# Sheet_MAGJACK.net
KiCad netlist of a schematic drawn in Altium Designer
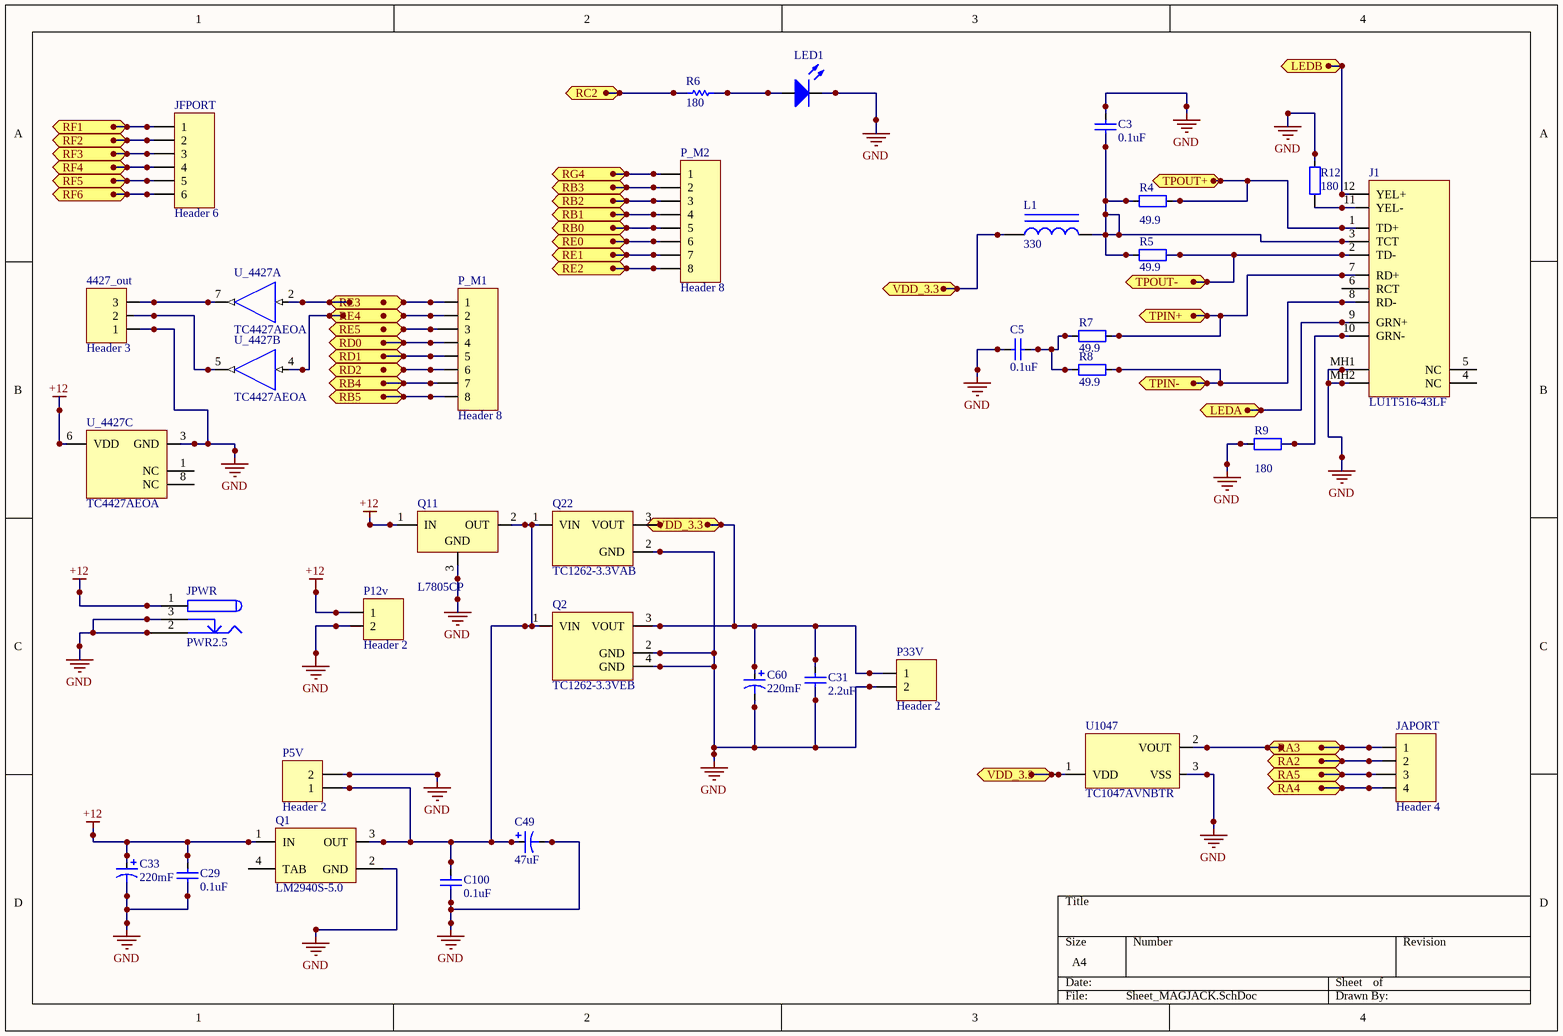
[diagram p0: Sheet_MAGJACK.SchDoc]

(export (version "E")
  (design (tool "Eeschema 10.0.6"))
  (components
    (comp (ref "4427_out")
      (value "Header 3")
      (footprint "BIG4")
      (description "Header, 3-Pin")
      (fields (field (name "PUBLISHER") "Altium Limited"))
      (libsource (lib "Miscellaneous Connectors") (part "Header 3"))
    )
    (comp (ref "C3")
      (value "0.1uF")
      (footprint "CAPC2012L")
      (description "Capacitor")
      (fields (field (name "PUBLISHER") "Altium Limited"))
      (libsource (lib "Miscellaneous Devices") (part "Cap"))
    )
    (comp (ref "C5")
      (value "0.1uF")
      (footprint "CAPC2012L")
      (description "Capacitor")
      (fields (field (name "PUBLISHER") "Altium Limited"))
      (libsource (lib "Miscellaneous Devices") (part "Cap"))
    )
    (comp (ref "C29")
      (value "0.1uF")
      (footprint "CAPC2012L")
      (description "Capacitor")
      (fields (field (name "PUBLISHER") "Altium Limited"))
      (libsource (lib "Miscellaneous Devices") (part "Cap"))
    )
    (comp (ref "C31")
      (value "2.2uF")
      (footprint "CAPC3216L")
      (description "Capacitor")
      (fields (field (name "PUBLISHER") "Altium Limited"))
      (libsource (lib "Miscellaneous Devices") (part "Cap"))
    )
    (comp (ref "C33")
      (value "220mF")
      (footprint "CAPPR5-10x12.5")
      (description "Polarized Capacitor (Radial)")
      (fields (field (name "PUBLISHER") "Altium Limited"))
      (libsource (lib "Miscellaneous Devices") (part "Cap Pol1"))
    )
    (comp (ref "C49")
      (value "47uF")
      (footprint "NSOALUMB")
      (description "Polarized Capacitor (Radial)")
      (fields (field (name "PUBLISHER") "Altium Limited"))
      (libsource (lib "Miscellaneous Devices") (part "Cap Pol1"))
    )
    (comp (ref "C60")
      (value "220mF")
      (footprint "CAPPR5-10x12.5")
      (description "Polarized Capacitor (Radial)")
      (fields (field (name "PUBLISHER") "Altium Limited"))
      (libsource (lib "Miscellaneous Devices") (part "Cap Pol1"))
    )
    (comp (ref "C100")
      (value "0.1uF")
      (footprint "CAPC2012L")
      (description "Capacitor (Semiconductor SIM Model)")
      (fields (field (name "PUBLISHER") "Altium Limited"))
      (libsource (lib "Miscellaneous Devices") (part "Cap Semi"))
    )
    (comp (ref "J1")
      (value "LU1T516-43LF")
      (footprint "CON_RJ45_RA_LEDS")
      (libsource (lib "MagJack") (part "Component_1"))
    )
    (comp (ref "JAPORT")
      (value "Header 4")
      (footprint "HDR1X4")
      (description "Header, 4-Pin")
      (fields (field (name "PUBLISHER") "Altium Limited"))
      (libsource (lib "Miscellaneous Connectors") (part "Header 4"))
    )
    (comp (ref "JFPORT")
      (value "Header 6")
      (footprint "HDR1X6")
      (description "Header, 6-Pin")
      (fields (field (name "PUBLISHER") "Altium Limited"))
      (libsource (lib "Miscellaneous Connectors") (part "Header 6"))
    )
    (comp (ref "JPWR")
      (value "PWR2.5")
      (footprint "KLD-0202")
      (description "DC Power Jack, 2.5mm, KLD Series, PCB Mount")
      (fields (field (name "PUBLISHER") "Altium Limited"))
      (libsource (lib "PCB_4550") (part "PWR2.5"))
    )
    (comp (ref "L1")
      (value "330")
      (footprint "RESC2012L")
      (description "Magnetic-Core Inductor")
      (fields (field (name "PUBLISHER") "Altium Limited"))
      (libsource (lib "Miscellaneous Devices") (part "Inductor Iron"))
    )
    (comp (ref "LED1")
      (value "LED2")
      (footprint "CAPC2012L")
      (description "Typical RED, GREEN, YELLOW, AMBER GaAs LED")
      (fields (field (name "PUBLISHER") "Altium Limited"))
      (libsource (lib "Miscellaneous Devices") (part "LED2"))
    )
    (comp (ref "P5V")
      (value "Header 2")
      (footprint "HDR1X2")
      (description "Header, 2-Pin")
      (fields (field (name "PUBLISHER") "Altium Limited"))
      (libsource (lib "Miscellaneous Connectors") (part "Header 2"))
    )
    (comp (ref "P12v")
      (value "Header 2")
      (footprint "HDR1X2")
      (description "Header, 2-Pin")
      (fields (field (name "PUBLISHER") "Altium Limited"))
      (libsource (lib "") (part "Header 2_1"))
    )
    (comp (ref "P33V")
      (value "Header 2")
      (footprint "HDR1X2")
      (description "Header, 2-Pin")
      (fields (field (name "PUBLISHER") "Altium Limited"))
      (libsource (lib "") (part "Header 2_1"))
    )
    (comp (ref "P_M1")
      (value "Header 8")
      (footprint "HDR1X8")
      (description "Header, 8-Pin")
      (fields (field (name "PUBLISHER") "Altium Limited"))
      (libsource (lib "Miscellaneous Connectors") (part "Header 8"))
    )
    (comp (ref "P_M2")
      (value "Header 8")
      (footprint "HDR1X8")
      (description "Header, 8-Pin")
      (fields (field (name "PUBLISHER") "Altium Limited"))
      (libsource (lib "Miscellaneous Connectors") (part "Header 8"))
    )
    (comp (ref "Q1")
      (value "LM2940S-5.0")
      (footprint "TS3B_N")
      (description "1A Low Dropout Regulator")
      (fields
        (field (name "MANUFACTURER") "National Semiconductor")
        (field (name "DIGIKEYPARTNUMBER") "LM2940S-5.0-ND")
        (field (name "PUBLISHER") "Altium Limited")
      )
      (libsource (lib "NSC LDO") (part "LM2940S-5.0"))
    )
    (comp (ref "Q2")
      (value "TC1262-3.3VEB")
      (footprint "DDPAK-EB3_N")
      (description "500mA Fixed Output CMOS LDO, 3-Pin DDPAK, Extended Temperature")
      (fields (field (name "PUBLISHER") "Altium Limited"))
      (libsource (lib "Microchip Power Mgt Line Regulator") (part "TC1262-3.3VEB"))
    )
    (comp (ref "Q11")
      (value "L7805CP")
      (footprint "ISOWATT220AB")
      (description "Positive Voltage Regulator")
      (fields (field (name "PUBLISHER") "Altium Limited"))
      (libsource (lib "ST Power Mgt Voltage Regulator") (part "L7805CP"))
    )
    (comp (ref "Q22")
      (value "TC1262-3.3VAB")
      (footprint "TO-220-AB3")
      (description "500mA Fixed Output CMOS LDO, 3-Pin TO-220, Extended Temperature")
      (fields (field (name "PUBLISHER") "Altium Limited"))
      (libsource (lib "Microchip Power Mgt Line Regulator") (part "TC1262-3.3VAB"))
    )
    (comp (ref "R4")
      (value "49.9")
      (footprint "RESC2012L")
      (description "Resistor")
      (fields (field (name "PUBLISHER") "Altium Limited"))
      (libsource (lib "Miscellaneous Devices") (part "Res2"))
    )
    (comp (ref "R5")
      (value "49.9")
      (footprint "RESC2012L")
      (description "Resistor")
      (fields (field (name "PUBLISHER") "Altium Limited"))
      (libsource (lib "Miscellaneous Devices") (part "Res2"))
    )
    (comp (ref "R6")
      (value "180")
      (footprint "RESC2012L")
      (description "Semiconductor Resistor")
      (fields (field (name "PUBLISHER") "Altium Limited"))
      (libsource (lib "Miscellaneous Devices") (part "Res Semi"))
    )
    (comp (ref "R7")
      (value "49.9")
      (footprint "RESC2012L")
      (description "Resistor")
      (fields (field (name "PUBLISHER") "Altium Limited"))
      (libsource (lib "Miscellaneous Devices") (part "Res2"))
    )
    (comp (ref "R8")
      (value "49.9")
      (footprint "RESC2012L")
      (description "Resistor")
      (fields (field (name "PUBLISHER") "Altium Limited"))
      (libsource (lib "Miscellaneous Devices") (part "Res2"))
    )
    (comp (ref "R9")
      (value "180")
      (footprint "RESC2012L")
      (description "Resistor")
      (fields (field (name "PUBLISHER") "Altium Limited"))
      (libsource (lib "Miscellaneous Devices") (part "Res2"))
    )
    (comp (ref "R12")
      (value "180")
      (footprint "RESC2012L")
      (description "Resistor")
      (fields (field (name "PUBLISHER") "Altium Limited"))
      (libsource (lib "") (part "Res2_1"))
    )
    (comp (ref "U1047")
      (value "TC1047AVNBTR")
      (footprint "SOT-23-NB3_N")
      (description "Precision Temperature-to-Voltage Converter, 3-Pin SOT-23, Extended Temperature, Tape and Reel")
      (fields (field (name "PUBLISHER") "Altium Limited"))
      (libsource (lib "Microchip Thermal Management") (part "TC1047AVNBTR"))
    )
    (comp (ref "U_4427")
      (value "TC4427AEOA")
      (footprint "SOIC-OA8_N")
      (description "1.5A Dual High-Speed Power MOSFET Driver, Non-Inverting, Industrial Temperature")
      (fields (field (name "PUBLISHER") "Altium Limited"))
      (libsource (lib "Microchip Power Mgt MOSFET Driver") (part "TC4427AEOA"))
    )
  )
  (nets
    (net (code "1") (name "+12") (class "Default")
      (node (ref "C29") (pin "2") (pinfunction "2_2") (pintype "passive"))
      (node (ref "C33") (pin "1") (pinfunction "1_1") (pintype "passive"))
      (node (ref "JPWR") (pin "1") (pinfunction "1_1") (pintype "power_in"))
      (node (ref "JPWR") (pin "1A") (pinfunction "1A_1A") (pintype "power_in"))
      (node (ref "JPWR") (pin "1B") (pinfunction "1B_1B") (pintype "power_in"))
      (node (ref "P12v") (pin "1") (pinfunction "1_1") (pintype "passive"))
      (node (ref "Q1") (pin "1") (pinfunction "IN_1") (pintype "power_in"))
      (node (ref "Q11") (pin "1") (pinfunction "IN_1") (pintype "power_in"))
      (node (ref "U_4427") (pin "6") (pinfunction "VDD_6") (pintype "power_in"))
    )
    (net (code "2") (name "/LEDA") (class "Default")
      (node (ref "J1") (pin "9") (pinfunction "GRN+_9") (pintype "passive"))
    )
    (net (code "3") (name "/LEDB") (class "Default")
      (node (ref "J1") (pin "12") (pinfunction "YEL+_12") (pintype "passive"))
    )
    (net (code "4") (name "/RA2") (class "Default")
      (node (ref "JAPORT") (pin "2") (pinfunction "2_2") (pintype "passive"))
    )
    (net (code "5") (name "/RA3") (class "Default")
      (node (ref "JAPORT") (pin "1") (pinfunction "1_1") (pintype "passive"))
      (node (ref "U1047") (pin "2") (pinfunction "VOUT_2") (pintype "power_in"))
    )
    (net (code "6") (name "/RA4") (class "Default")
      (node (ref "JAPORT") (pin "4") (pinfunction "4_4") (pintype "passive"))
    )
    (net (code "7") (name "/RA5") (class "Default")
      (node (ref "JAPORT") (pin "3") (pinfunction "3_3") (pintype "passive"))
    )
    (net (code "8") (name "/RB0") (class "Default")
      (node (ref "P_M2") (pin "5") (pinfunction "5_5") (pintype "passive"))
    )
    (net (code "9") (name "/RB1") (class "Default")
      (node (ref "P_M2") (pin "4") (pinfunction "4_4") (pintype "passive"))
    )
    (net (code "10") (name "/RB2") (class "Default")
      (node (ref "P_M2") (pin "3") (pinfunction "3_3") (pintype "passive"))
    )
    (net (code "11") (name "/RB3") (class "Default")
      (node (ref "P_M2") (pin "2") (pinfunction "2_2") (pintype "passive"))
    )
    (net (code "12") (name "/RB4") (class "Default")
      (node (ref "P_M1") (pin "7") (pinfunction "7_7") (pintype "passive"))
    )
    (net (code "13") (name "/RB5") (class "Default")
      (node (ref "P_M1") (pin "8") (pinfunction "8_8") (pintype "passive"))
    )
    (net (code "14") (name "/RC2") (class "Default")
      (node (ref "R6") (pin "1") (pinfunction "1_1") (pintype "passive"))
    )
    (net (code "15") (name "/RD0") (class "Default")
      (node (ref "P_M1") (pin "4") (pinfunction "4_4") (pintype "passive"))
    )
    (net (code "16") (name "/RD1") (class "Default")
      (node (ref "P_M1") (pin "5") (pinfunction "5_5") (pintype "passive"))
    )
    (net (code "17") (name "/RD2") (class "Default")
      (node (ref "P_M1") (pin "6") (pinfunction "6_6") (pintype "passive"))
    )
    (net (code "18") (name "/RE0") (class "Default")
      (node (ref "P_M2") (pin "6") (pinfunction "6_6") (pintype "passive"))
    )
    (net (code "19") (name "/RE1") (class "Default")
      (node (ref "P_M2") (pin "7") (pinfunction "7_7") (pintype "passive"))
    )
    (net (code "20") (name "/RE2") (class "Default")
      (node (ref "P_M2") (pin "8") (pinfunction "8_8") (pintype "passive"))
    )
    (net (code "21") (name "/RE3") (class "Default")
      (node (ref "P_M1") (pin "1") (pinfunction "1_1") (pintype "passive"))
      (node (ref "U_4427") (pin "2") (pinfunction "INA_2") (pintype "input"))
    )
    (net (code "22") (name "/RE4") (class "Default")
      (node (ref "P_M1") (pin "2") (pinfunction "2_2") (pintype "passive"))
      (node (ref "U_4427") (pin "4") (pinfunction "INB_4") (pintype "input"))
    )
    (net (code "23") (name "/RE5") (class "Default")
      (node (ref "P_M1") (pin "3") (pinfunction "3_3") (pintype "passive"))
    )
    (net (code "24") (name "/RF1") (class "Default")
      (node (ref "JFPORT") (pin "1") (pinfunction "1_1") (pintype "passive"))
    )
    (net (code "25") (name "/RF2") (class "Default")
      (node (ref "JFPORT") (pin "2") (pinfunction "2_2") (pintype "passive"))
    )
    (net (code "26") (name "/RF3") (class "Default")
      (node (ref "JFPORT") (pin "3") (pinfunction "3_3") (pintype "passive"))
    )
    (net (code "27") (name "/RF4") (class "Default")
      (node (ref "JFPORT") (pin "4") (pinfunction "4_4") (pintype "passive"))
    )
    (net (code "28") (name "/RF5") (class "Default")
      (node (ref "JFPORT") (pin "5") (pinfunction "5_5") (pintype "passive"))
    )
    (net (code "29") (name "/RF6") (class "Default")
      (node (ref "JFPORT") (pin "6") (pinfunction "6_6") (pintype "passive"))
    )
    (net (code "30") (name "/RG4") (class "Default")
      (node (ref "P_M2") (pin "1") (pinfunction "1_1") (pintype "passive"))
    )
    (net (code "31") (name "/TPIN+") (class "Default")
      (node (ref "J1") (pin "7") (pinfunction "RD+_7") (pintype "passive"))
      (node (ref "R7") (pin "2") (pinfunction "2_2") (pintype "passive"))
    )
    (net (code "32") (name "/TPIN-") (class "Default")
      (node (ref "J1") (pin "8") (pinfunction "RD-_8") (pintype "passive"))
      (node (ref "R8") (pin "2") (pinfunction "2_2") (pintype "passive"))
    )
    (net (code "33") (name "/TPOUT+") (class "Default")
      (node (ref "J1") (pin "1") (pinfunction "TD+_1") (pintype "passive"))
      (node (ref "R4") (pin "2") (pinfunction "2_2") (pintype "passive"))
    )
    (net (code "34") (name "/TPOUT-") (class "Default")
      (node (ref "J1") (pin "2") (pinfunction "TD-_2") (pintype "passive"))
      (node (ref "R5") (pin "2") (pinfunction "2_2") (pintype "passive"))
    )
    (net (code "35") (name "/VDD_3.3") (class "Default")
      (node (ref "C31") (pin "2") (pinfunction "2_2") (pintype "passive"))
      (node (ref "C60") (pin "1") (pinfunction "1_1") (pintype "passive"))
      (node (ref "L1") (pin "1") (pinfunction "1_1") (pintype "passive"))
      (node (ref "P33V") (pin "1") (pinfunction "1_1") (pintype "passive"))
      (node (ref "Q2") (pin "3") (pinfunction "VOUT_3") (pintype "power_in"))
      (node (ref "U1047") (pin "1") (pinfunction "VDD_1") (pintype "power_in"))
    )
    (net (code "36") (name "GND") (class "Default")
      (node (ref "4427_out") (pin "1") (pinfunction "1_1") (pintype "passive"))
      (node (ref "C100") (pin "1") (pinfunction "1_1") (pintype "passive"))
      (node (ref "C29") (pin "1") (pinfunction "1_1") (pintype "passive"))
      (node (ref "C3") (pin "2") (pinfunction "2_2") (pintype "passive"))
      (node (ref "C31") (pin "1") (pinfunction "1_1") (pintype "passive"))
      (node (ref "C33") (pin "2") (pinfunction "2_2") (pintype "passive"))
      (node (ref "C49") (pin "2") (pinfunction "2_2") (pintype "passive"))
      (node (ref "C5") (pin "1") (pinfunction "1_1") (pintype "passive"))
      (node (ref "C60") (pin "2") (pinfunction "2_2") (pintype "passive"))
      (node (ref "J1") (pin "MH1") (pinfunction "MH1_MH1") (pintype "passive"))
      (node (ref "J1") (pin "MH2") (pinfunction "MH2_MH2") (pintype "passive"))
      (node (ref "JPWR") (pin "2") (pinfunction "2_2") (pintype "power_in"))
      (node (ref "JPWR") (pin "2A") (pinfunction "2A_2A") (pintype "power_in"))
      (node (ref "JPWR") (pin "2B") (pinfunction "2B_2B") (pintype "power_in"))
      (node (ref "JPWR") (pin "3") (pinfunction "3_3") (pintype "power_in"))
      (node (ref "JPWR") (pin "3A") (pinfunction "3A_3A") (pintype "power_in"))
      (node (ref "JPWR") (pin "3B") (pinfunction "3B_3B") (pintype "power_in"))
      (node (ref "LED1") (pin "2") (pinfunction "K_2") (pintype "passive"))
      (node (ref "P12v") (pin "2") (pinfunction "2_2") (pintype "passive"))
      (node (ref "P33V") (pin "2") (pinfunction "2_2") (pintype "passive"))
      (node (ref "P5V") (pin "2") (pinfunction "2_2") (pintype "passive"))
      (node (ref "Q1") (pin "2") (pinfunction "GND_2") (pintype "power_in"))
      (node (ref "Q11") (pin "3") (pinfunction "GND_3") (pintype "power_in"))
      (node (ref "Q2") (pin "2") (pinfunction "GND_2") (pintype "power_in"))
      (node (ref "Q2") (pin "4") (pinfunction "GND_4") (pintype "power_in"))
      (node (ref "Q22") (pin "2") (pinfunction "GND_2") (pintype "power_in"))
      (node (ref "R12") (pin "2") (pinfunction "2_2") (pintype "passive"))
      (node (ref "R9") (pin "1") (pinfunction "1_1") (pintype "passive"))
      (node (ref "U1047") (pin "3") (pinfunction "VSS_3") (pintype "power_in"))
      (node (ref "U_4427") (pin "3") (pinfunction "GND_3") (pintype "power_in"))
    )
    (net (code "37") (name "Net-(C5-Pad2)") (class "Default")
      (node (ref "C5") (pin "2") (pinfunction "2_2") (pintype "passive"))
      (node (ref "R7") (pin "1") (pinfunction "1_1") (pintype "passive"))
      (node (ref "R8") (pin "1") (pinfunction "1_1") (pintype "passive"))
    )
    (net (code "38") (name "Net-(J1-GRN-)") (class "Default")
      (node (ref "J1") (pin "10") (pinfunction "GRN-_10") (pintype "passive"))
      (node (ref "R9") (pin "2") (pinfunction "2_2") (pintype "passive"))
    )
    (net (code "39") (name "Net-(J1-TCT)") (class "Default")
      (node (ref "C3") (pin "1") (pinfunction "1_1") (pintype "passive"))
      (node (ref "J1") (pin "3") (pinfunction "TCT_3") (pintype "passive"))
      (node (ref "L1") (pin "2") (pinfunction "2_2") (pintype "passive"))
      (node (ref "R4") (pin "1") (pinfunction "1_1") (pintype "passive"))
      (node (ref "R5") (pin "1") (pinfunction "1_1") (pintype "passive"))
    )
    (net (code "40") (name "Net-(J1-YEL-)") (class "Default")
      (node (ref "J1") (pin "11") (pinfunction "YEL-_11") (pintype "passive"))
      (node (ref "R12") (pin "1") (pinfunction "1_1") (pintype "passive"))
    )
    (net (code "41") (name "Net-(LED1-A)") (class "Default")
      (node (ref "LED1") (pin "1") (pinfunction "A_1") (pintype "passive"))
      (node (ref "R6") (pin "2") (pinfunction "2_2") (pintype "passive"))
    )
    (net (code "42") (name "Net-(Q1-OUT)") (class "Default")
      (node (ref "C100") (pin "2") (pinfunction "2_2") (pintype "passive"))
      (node (ref "C49") (pin "1") (pinfunction "1_1") (pintype "passive"))
      (node (ref "P5V") (pin "1") (pinfunction "1_1") (pintype "passive"))
      (node (ref "Q1") (pin "3") (pinfunction "OUT_3") (pintype "power_in"))
      (node (ref "Q11") (pin "2") (pinfunction "OUT_2") (pintype "power_in"))
      (node (ref "Q2") (pin "1") (pinfunction "VIN_1") (pintype "power_in"))
      (node (ref "Q22") (pin "1") (pinfunction "VIN_1") (pintype "power_in"))
    )
    (net (code "43") (name "Net-(U_4427A-OUTA)") (class "Default")
      (node (ref "4427_out") (pin "3") (pinfunction "3_3") (pintype "passive"))
      (node (ref "U_4427") (pin "7") (pinfunction "OUTA_7") (pintype "output"))
    )
    (net (code "44") (name "Net-(U_4427B-OUTB)") (class "Default")
      (node (ref "4427_out") (pin "2") (pinfunction "2_2") (pintype "passive"))
      (node (ref "U_4427") (pin "5") (pinfunction "OUTB_5") (pintype "output"))
    )
    (net (code "45") (name "unconnected-(J1-NC-Pad4)") (class "Default")
      (node (ref "J1") (pin "4") (pinfunction "NC_4") (pintype "passive"))
    )
    (net (code "46") (name "unconnected-(J1-NC-Pad5)") (class "Default")
      (node (ref "J1") (pin "5") (pinfunction "NC_5") (pintype "passive"))
    )
    (net (code "47") (name "unconnected-(J1-RCT-Pad6)") (class "Default")
      (node (ref "J1") (pin "6") (pinfunction "RCT_6") (pintype "passive"))
    )
    (net (code "48") (name "unconnected-(Q1-TAB-Pad4)") (class "Default")
      (node (ref "Q1") (pin "4") (pinfunction "TAB_4") (pintype "power_in"))
    )
    (net (code "49") (name "unconnected-(Q22-VOUT-Pad3)") (class "Default")
      (node (ref "Q22") (pin "3") (pinfunction "VOUT_3") (pintype "power_in"))
    )
    (net (code "50") (name "unconnected-(U_4427C-NC-Pad1)") (class "Default")
      (node (ref "U_4427") (pin "1") (pinfunction "NC_1") (pintype "passive"))
    )
    (net (code "51") (name "unconnected-(U_4427C-NC-Pad8)") (class "Default")
      (node (ref "U_4427") (pin "8") (pinfunction "NC_8") (pintype "passive"))
    )
  )
)
